# Serial.net
KiCad netlist of a schematic drawn in Altium Designer
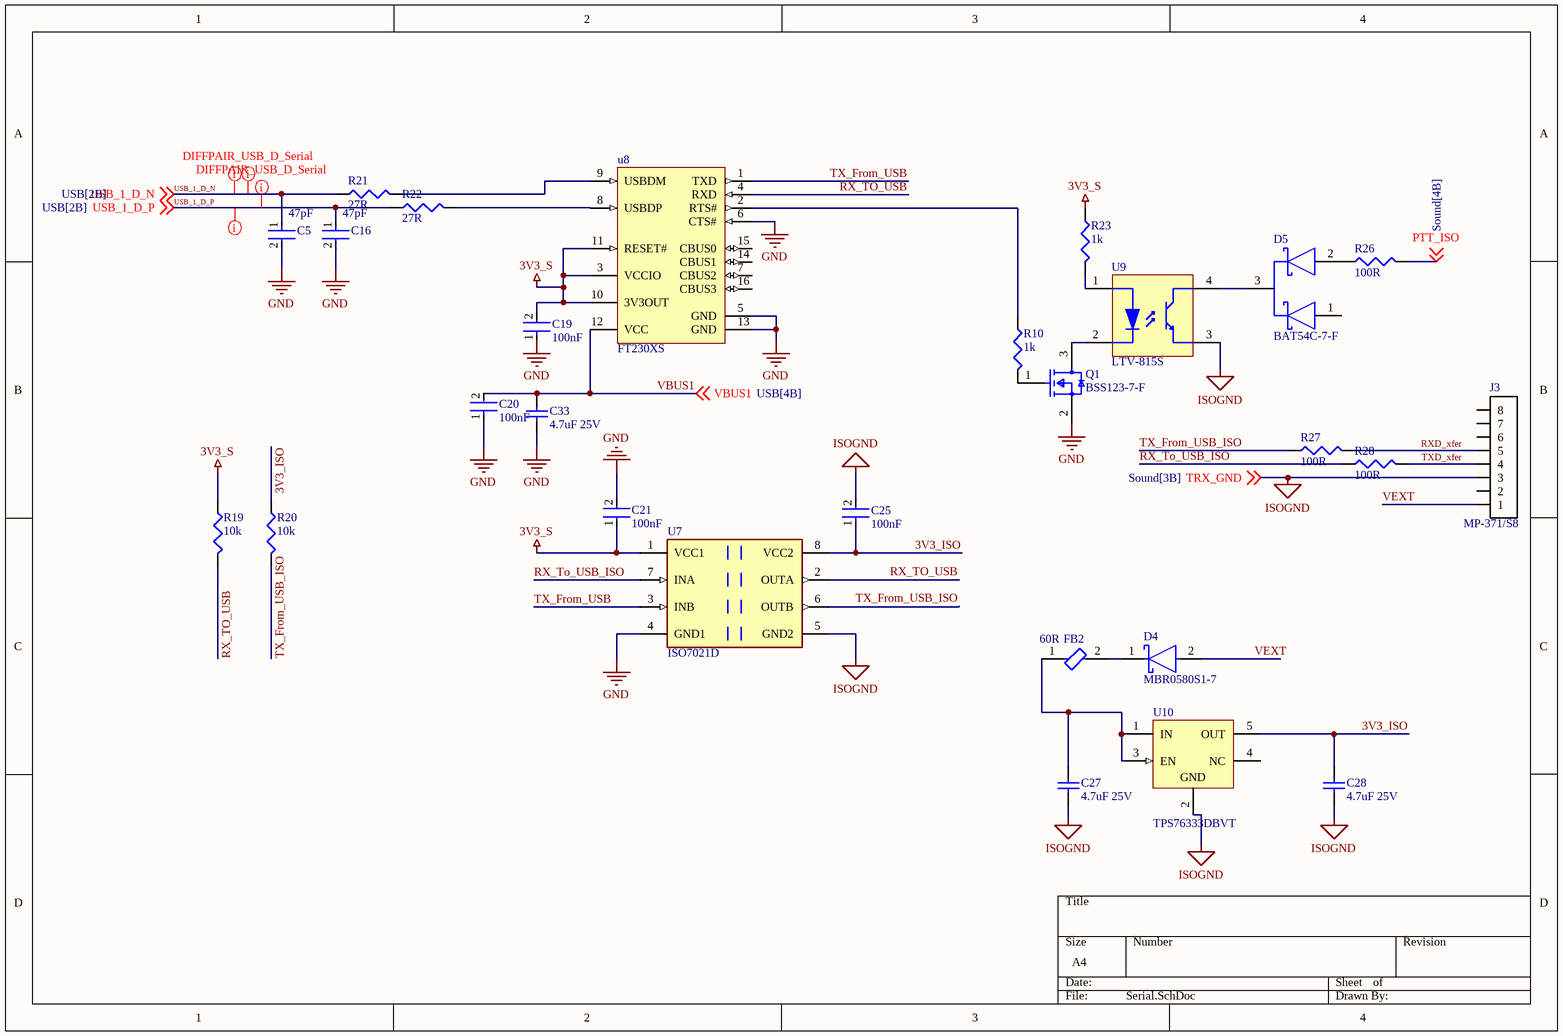
[diagram p0: Serial.SchDoc]

(export (version "E")
  (design (tool "Eeschema 10.0.6"))
  (components
    (comp (ref "C5")
      (value "CL10C470JC8NNNC")
      (footprint "FP-CL10-IPC_C")
      (description "Cap Ceramic 47pF 100V C0G ±5% Pad SMD 0603 +125°C T/R")
      (fields
        (field (name "TOLERANCE") "5%")
        (field (name "CAPACITANCE") "47pF")
        (field (name "JLCPCBPARTNUM") "C1671")
      )
      (libsource (lib "Altium Content Vault") (part "b4654b650e69147ec39a6b967a45e02"))
    )
    (comp (ref "C16")
      (value "CL10C470JC8NNNC")
      (footprint "FP-CL10-IPC_C")
      (description "Cap Ceramic 47pF 100V C0G ±5% Pad SMD 0603 +125°C T/R")
      (fields
        (field (name "TOLERANCE") "5%")
        (field (name "CAPACITANCE") "47pF")
        (field (name "JLCPCBPARTNUM") "C1671")
      )
      (libsource (lib "Altium Content Vault") (part "b4654b650e69147ec39a6b967a45e02"))
    )
    (comp (ref "C19")
      (value "CL10B104KC8NNNC")
      (footprint "FP-CL10-IPC_B")
      (description "Cap Ceramic 100nF 100V X7R ±10% Pad SMD 0603 +125°C T/R")
      (fields
        (field (name "TOLERANCE") "10%")
        (field (name "CAPACITANCE") "100nF")
        (field (name "JLCPCBPARTNUM") "C15725")
      )
      (libsource (lib "Altium Content Vault") (part "b4654b650e69147ec39a6b967a45e02"))
    )
    (comp (ref "C20")
      (value "CL10B104KC8NNNC")
      (footprint "FP-CL10-IPC_B")
      (description "Cap Ceramic 100nF 100V X7R ±10% Pad SMD 0603 +125°C T/R")
      (fields
        (field (name "TOLERANCE") "10%")
        (field (name "CAPACITANCE") "100nF")
        (field (name "JLCPCBPARTNUM") "C15725")
      )
      (libsource (lib "Altium Content Vault") (part "b4654b650e69147ec39a6b967a45e02"))
    )
    (comp (ref "C21")
      (value "CL10B104KC8NNNC")
      (footprint "FP-CL10-IPC_B")
      (description "Cap Ceramic 100nF 100V X7R ±10% Pad SMD 0603 +125°C T/R")
      (fields
        (field (name "TOLERANCE") "10%")
        (field (name "CAPACITANCE") "100nF")
        (field (name "JLCPCBPARTNUM") "C15725")
      )
      (libsource (lib "Altium Content Vault") (part "b4654b650e69147ec39a6b967a45e02"))
    )
    (comp (ref "C25")
      (value "CL10B104KC8NNNC")
      (footprint "FP-CL10-IPC_B")
      (description "Cap Ceramic 100nF 100V X7R ±10% Pad SMD 0603 +125°C T/R")
      (fields
        (field (name "TOLERANCE") "10%")
        (field (name "CAPACITANCE") "100nF")
        (field (name "JLCPCBPARTNUM") "C15725")
      )
      (libsource (lib "Altium Content Vault") (part "b4654b650e69147ec39a6b967a45e02"))
    )
    (comp (ref "C27")
      (value "4.7uF 25V")
      (footprint "CAPC1210(3225)220_M")
      (description "CAP 4.7uF 25V ±10% 1210 (3225 Metric) Thickness 2.2mm SMD")
      (fields (field (name "TOLERANCE") "Â±10%") (field (name "JLCPCBPARTNUM") "C86052"))
      (libsource (lib "Altium Content Vault") (part "CAP"))
    )
    (comp (ref "C28")
      (value "4.7uF 25V")
      (footprint "CAPC1210(3225)220_M")
      (description "CAP 4.7uF 25V ±10% 1210 (3225 Metric) Thickness 2.2mm SMD")
      (fields (field (name "TOLERANCE") "Â±10%") (field (name "JLCPCBPARTNUM") "C86052"))
      (libsource (lib "Altium Content Vault") (part "CAP"))
    )
    (comp (ref "C33")
      (value "4.7uF 25V")
      (footprint "CAPC1210(3225)220_M")
      (description "CAP 4.7uF 25V ±10% 1210 (3225 Metric) Thickness 2.2mm SMD")
      (fields (field (name "TOLERANCE") "Â±10%") (field (name "JLCPCBPARTNUM") "C86052"))
      (libsource (lib "Altium Content Vault") (part "CAP"))
    )
    (comp (ref "D4")
      (value "MBR0580S1-7")
      (footprint "FP-SOD123-MFG")
      (description "DIODE SCHOTTKY 80V 500MA SOD123")
      (fields
        (field (name "OCTOPART") "https://octopart.com/mbr0580s1-7-diodes+inc.-53081572")
        (field (name "MANUFACTURER") "Diodes")
      )
      (libsource (lib "Altium Content Vault") (part "1d6ec82d83fb6aee721767c19dac4b9"))
    )
    (comp (ref "D5")
      (value "BAT54C-7-F")
      (footprint "FP-SOT23-IPC_B")
      (description "DIODE ARRAY SCHOTTKY 30V SOT23-3")
      (fields (field (name "JLCPCBPARTNUM") "C134405"))
      (libsource (lib "Altium Content Vault") (part "3eac2aa0c1ac86323ecc23460aa29c6"))
    )
    (comp (ref "FB2")
      (value "BLM41PG600SN1L")
      (footprint "FP-BLM41-0_2-IPC_B")
      (description "Ferrite Bead, 1806, 60Ω @ 100MHz, 0.009Ω, 6A")
      (fields
        (field (name "TOLERANCE") "25%")
        (field (name "IMPEDANCE") "60R")
        (field (name "JLCPCBPARTNUM") "C85844")
      )
      (libsource (lib "Altium Content Vault") (part "5f30dd21d616792df468990f7003faa"))
    )
    (comp (ref "J3")
      (value "MP-371/S8")
      (footprint "MiniDIN8_TopSolder_Lumberg")
      (description "Miniature circular connectors MP-371/S8")
      (fields (field (name "DIGIKEY_PARTNUM") "2057-MDP-008-ND"))
      (libsource (lib "Schlib1") (part "MiniDin8_SMT"))
    )
    (comp (ref "Q1")
      (value "BSS123-7-F")
      (footprint "FP-SOT23-IPC_C")
      (description "MOSFET N-CH 100V 170MA SOT23-3")
      (fields
        (field (name "OCTOPART") "https://octopart.com/bss123-7-f-diodes+inc.-335886")
        (field (name "MANUFACTURER") "Diodes Incorporated")
      )
      (libsource (lib "Altium Content Vault") (part "1661867509f36a4ffa577829538a895"))
    )
    (comp (ref "R10")
      (value "1k")
      (footprint "J1-0603")
      (description "Resistor")
      (fields (field (name "JLCPCBPARTNUM") "C21190") (field (name "PUBLISHER") "Altium Limited"))
      (libsource (lib "Miscellaneous Devices") (part "Res3"))
    )
    (comp (ref "R19")
      (value "10k")
      (footprint "J1-0603")
      (description "Resistor")
      (fields (field (name "JLCPCBPARTNUM") "C25804") (field (name "PUBLISHER") "Altium Limited"))
      (libsource (lib "Miscellaneous Devices") (part "Res3"))
    )
    (comp (ref "R20")
      (value "10k")
      (footprint "J1-0603")
      (description "Resistor")
      (fields (field (name "JLCPCBPARTNUM") "C25804") (field (name "PUBLISHER") "Altium Limited"))
      (libsource (lib "Miscellaneous Devices") (part "Res3"))
    )
    (comp (ref "R21")
      (value "27R")
      (footprint "J1-0603")
      (description "Resistor")
      (fields (field (name "JLCPCBPARTNUM") "C192531") (field (name "PUBLISHER") "Altium Limited"))
      (libsource (lib "Miscellaneous Devices") (part "Res3"))
    )
    (comp (ref "R22")
      (value "27R")
      (footprint "J1-0603")
      (description "Resistor")
      (fields (field (name "JLCPCBPARTNUM") "C192531") (field (name "PUBLISHER") "Altium Limited"))
      (libsource (lib "Miscellaneous Devices") (part "Res3"))
    )
    (comp (ref "R23")
      (value "1k")
      (footprint "J1-0603")
      (description "Resistor")
      (fields (field (name "JLCPCBPARTNUM") "C21190") (field (name "PUBLISHER") "Altium Limited"))
      (libsource (lib "Miscellaneous Devices") (part "Res3"))
    )
    (comp (ref "R26")
      (value "100R")
      (footprint "J1-0603")
      (description "Resistor")
      (fields (field (name "JLCPCBPARTNUM") "C22775") (field (name "PUBLISHER") "Altium Limited"))
      (libsource (lib "Miscellaneous Devices") (part "Res3"))
    )
    (comp (ref "R27")
      (value "100R")
      (footprint "J1-0603")
      (description "Resistor")
      (fields (field (name "JLCPCBPARTNUM") "C22775") (field (name "PUBLISHER") "Altium Limited"))
      (libsource (lib "Miscellaneous Devices") (part "Res3"))
    )
    (comp (ref "R28")
      (value "100R")
      (footprint "J1-0603")
      (description "Resistor")
      (fields (field (name "JLCPCBPARTNUM") "C22775") (field (name "PUBLISHER") "Altium Limited"))
      (libsource (lib "Miscellaneous Devices") (part "Res3"))
    )
    (comp (ref "U7")
      (value "ISO7021D")
      (footprint "FP-D0008A-IPC_B")
      (description "DGTL ISO 3000VRMS 2CH GP 8SOIC")
      (libsource (lib "Altium Content Vault") (part "defe170305b380fc4992fd481d2aa34"))
    )
    (comp (ref "u8")
      (value "FT230XS")
      (footprint "FTDI-SSOP-16_L")
      (description "USB to Basic UART IC, 2.97 to 5.5 V, -40 to 85 degC, 16-Pin SSOP, RoHS")
      (fields (field (name "MANUFACTURER") "FTDI") (field (name "JLCPCBPARTNUM") "C69082"))
      (libsource (lib "Altium Content Vault") (part "FTDI-FT230XS-SSOP-16"))
    )
    (comp (ref "U9")
      (value "LTV-815S")
      (footprint "LTST-LTV-817S-4_V")
      (description "Photocoupler - Phototransistor Output, 35 V VCEO, -50 to 110 degC, 4-Pin SMD, RoHS, Tape and Reel")
      (fields (field (name "MANUFACTURER") "Lite-On") (field (name "JLCPCBPARTNUM") "C115455"))
      (libsource (lib "Altium Content Vault") (part "LTST-LTV-817-4"))
    )
    (comp (ref "U10")
      (value "TPS76333DBVT")
      (footprint "DBV0005A_N")
      (fields (field (name "MANUFACTURER") "Texas Instruments") (field (name "JLCPCBPARTNUM") "C7100"))
      (libsource (lib "Altium Content Vault") (part "TI-TXX7XXXX-5"))
    )
  )
  (nets
    (net (code "1") (name "/3V3_ISO") (class "Default")
      (node (ref "C25") (pin "1") (pinfunction "1_1") (pintype "passive"))
      (node (ref "C28") (pin "1") (pinfunction "1_1") (pintype "passive"))
      (node (ref "R20") (pin "1") (pinfunction "1_1") (pintype "passive"))
      (node (ref "U10") (pin "5") (pinfunction "OUT_5") (pintype "power_in"))
      (node (ref "U7") (pin "8") (pinfunction "VCC2_8") (pintype "power_in"))
    )
    (net (code "2") (name "/RXD_xfer") (class "Default")
      (node (ref "J3") (pin "5") (pinfunction "5_5") (pintype "passive"))
      (node (ref "R27") (pin "2") (pinfunction "2_2") (pintype "passive"))
    )
    (net (code "3") (name "/RX_TO_USB") (class "Default")
      (node (ref "R19") (pin "2") (pinfunction "2_2") (pintype "passive"))
      (node (ref "U7") (pin "2") (pinfunction "OUTA_2") (pintype "output"))
      (node (ref "u8") (pin "4") (pinfunction "RXD_4") (pintype "input"))
    )
    (net (code "4") (name "/RX_To_USB_ISO") (class "Default")
      (node (ref "R28") (pin "1") (pinfunction "1_1") (pintype "passive"))
      (node (ref "U7") (pin "7") (pinfunction "INA_7") (pintype "input"))
    )
    (net (code "5") (name "/TXD_xfer") (class "Default")
      (node (ref "J3") (pin "4") (pinfunction "4_4") (pintype "passive"))
      (node (ref "R28") (pin "2") (pinfunction "2_2") (pintype "passive"))
    )
    (net (code "6") (name "/TX_From_USB") (class "Default")
      (node (ref "U7") (pin "3") (pinfunction "INB_3") (pintype "input"))
      (node (ref "u8") (pin "1") (pinfunction "TXD_1") (pintype "output"))
    )
    (net (code "7") (name "/TX_From_USB_ISO") (class "Default")
      (node (ref "R20") (pin "2") (pinfunction "2_2") (pintype "passive"))
      (node (ref "R27") (pin "1") (pinfunction "1_1") (pintype "passive"))
      (node (ref "U7") (pin "6") (pinfunction "OUTB_6") (pintype "output"))
    )
    (net (code "8") (name "/VEXT") (class "Default")
      (node (ref "D4") (pin "2") (pinfunction "A_2") (pintype "passive"))
      (node (ref "J3") (pin "1") (pinfunction "1_1") (pintype "passive"))
    )
    (net (code "9") (name "3V3_S") (class "Default")
      (node (ref "C19") (pin "2") (pinfunction "2_2") (pintype "passive"))
      (node (ref "C21") (pin "1") (pinfunction "1_1") (pintype "passive"))
      (node (ref "R19") (pin "1") (pinfunction "1_1") (pintype "passive"))
      (node (ref "R23") (pin "1") (pinfunction "1_1") (pintype "passive"))
      (node (ref "U7") (pin "1") (pinfunction "VCC1_1") (pintype "power_in"))
      (node (ref "u8") (pin "10") (pinfunction "3V3OUT_10") (pintype "power_in"))
      (node (ref "u8") (pin "11") (pinfunction "RESET#_11") (pintype "input"))
      (node (ref "u8") (pin "3") (pinfunction "VCCIO_3") (pintype "power_in"))
    )
    (net (code "10") (name "GND") (class "Default")
      (node (ref "C16") (pin "2") (pinfunction "2_2") (pintype "passive"))
      (node (ref "C19") (pin "1") (pinfunction "1_1") (pintype "passive"))
      (node (ref "C20") (pin "1") (pinfunction "1_1") (pintype "passive"))
      (node (ref "C21") (pin "2") (pinfunction "2_2") (pintype "passive"))
      (node (ref "C33") (pin "2") (pinfunction "2_2") (pintype "passive"))
      (node (ref "C5") (pin "2") (pinfunction "2_2") (pintype "passive"))
      (node (ref "Q1") (pin "2") (pinfunction "S_2") (pintype "passive"))
      (node (ref "U7") (pin "4") (pinfunction "GND1_4") (pintype "power_in"))
      (node (ref "u8") (pin "13") (pinfunction "GND_13") (pintype "power_in"))
      (node (ref "u8") (pin "5") (pinfunction "GND_5") (pintype "power_in"))
      (node (ref "u8") (pin "6") (pinfunction "CTS#_6") (pintype "input"))
    )
    (net (code "11") (name "ISOGND") (class "Default")
      (node (ref "C25") (pin "2") (pinfunction "2_2") (pintype "passive"))
      (node (ref "C27") (pin "2") (pinfunction "2_2") (pintype "passive"))
      (node (ref "C28") (pin "2") (pinfunction "2_2") (pintype "passive"))
      (node (ref "J3") (pin "3") (pinfunction "3_3") (pintype "passive"))
      (node (ref "U10") (pin "2") (pinfunction "GND_2") (pintype "power_in"))
      (node (ref "U7") (pin "5") (pinfunction "GND2_5") (pintype "power_in"))
      (node (ref "U9") (pin "3") (pinfunction "EMITTER_3") (pintype "passive"))
    )
    (net (code "12") (name "Net-(D4-C)") (class "Default")
      (node (ref "D4") (pin "1") (pinfunction "C_1") (pintype "passive"))
      (node (ref "FB2") (pin "2") (pinfunction "2_2") (pintype "passive"))
    )
    (net (code "13") (name "Net-(D5-2_ANODE)") (class "Default")
      (node (ref "D5") (pin "2") (pinfunction "2_ANODE_2") (pintype "passive"))
      (node (ref "R26") (pin "1") (pinfunction "1_1") (pintype "passive"))
    )
    (net (code "14") (name "Net-(D5-COMMON_CATHODE)") (class "Default")
      (node (ref "D5") (pin "3") (pinfunction "COMMON_CATHODE_3") (pintype "passive"))
      (node (ref "U9") (pin "4") (pinfunction "COLLECTOR_4") (pintype "passive"))
    )
    (net (code "15") (name "Net-(Q1-D)") (class "Default")
      (node (ref "Q1") (pin "3") (pinfunction "D_3") (pintype "passive"))
      (node (ref "U9") (pin "2") (pinfunction "CATHODE_2") (pintype "passive"))
    )
    (net (code "16") (name "Net-(Q1-G)") (class "Default")
      (node (ref "Q1") (pin "1") (pinfunction "G_1") (pintype "passive"))
      (node (ref "R10") (pin "2") (pinfunction "2_2") (pintype "passive"))
    )
    (net (code "17") (name "Net-(U9-ANODE)") (class "Default")
      (node (ref "R23") (pin "2") (pinfunction "2_2") (pintype "passive"))
      (node (ref "U9") (pin "1") (pinfunction "ANODE_1") (pintype "passive"))
    )
    (net (code "18") (name "Net-(U10-EN)") (class "Default")
      (node (ref "C27") (pin "1") (pinfunction "1_1") (pintype "passive"))
      (node (ref "FB2") (pin "1") (pinfunction "1_1") (pintype "passive"))
      (node (ref "U10") (pin "1") (pinfunction "IN_1") (pintype "power_in"))
      (node (ref "U10") (pin "3") (pinfunction "EN_3") (pintype "input"))
    )
    (net (code "19") (name "Net-(u8-RTS#)") (class "Default")
      (node (ref "R10") (pin "1") (pinfunction "1_1") (pintype "passive"))
      (node (ref "u8") (pin "2") (pinfunction "RTS#_2") (pintype "output"))
    )
    (net (code "20") (name "Net-(u8-USBDM)") (class "Default")
      (node (ref "R21") (pin "2") (pinfunction "2_2") (pintype "passive"))
      (node (ref "u8") (pin "9") (pinfunction "USBDM_9") (pintype "input"))
    )
    (net (code "21") (name "Net-(u8-USBDP)") (class "Default")
      (node (ref "R22") (pin "2") (pinfunction "2_2") (pintype "passive"))
      (node (ref "u8") (pin "8") (pinfunction "USBDP_8") (pintype "input"))
    )
    (net (code "22") (name "PTT_ISO") (class "Default")
      (node (ref "R26") (pin "2") (pinfunction "2_2") (pintype "passive"))
    )
    (net (code "23") (name "USB_1_D_N") (class "Default")
      (node (ref "C5") (pin "1") (pinfunction "1_1") (pintype "passive"))
      (node (ref "R21") (pin "1") (pinfunction "1_1") (pintype "passive"))
    )
    (net (code "24") (name "USB_1_D_P") (class "Default")
      (node (ref "C16") (pin "1") (pinfunction "1_1") (pintype "passive"))
      (node (ref "R22") (pin "1") (pinfunction "1_1") (pintype "passive"))
    )
    (net (code "25") (name "VBUS1") (class "Default")
      (node (ref "C20") (pin "2") (pinfunction "2_2") (pintype "passive"))
      (node (ref "C33") (pin "1") (pinfunction "1_1") (pintype "passive"))
      (node (ref "u8") (pin "12") (pinfunction "VCC_12") (pintype "power_in"))
    )
    (net (code "26") (name "unconnected-(D5-1_ANODE-Pad1)") (class "Default")
      (node (ref "D5") (pin "1") (pinfunction "1_ANODE_1") (pintype "passive"))
    )
    (net (code "27") (name "unconnected-(J3-Pad2)") (class "Default")
      (node (ref "J3") (pin "2") (pinfunction "2_2") (pintype "passive"))
    )
    (net (code "28") (name "unconnected-(J3-Pad6)") (class "Default")
      (node (ref "J3") (pin "6") (pinfunction "6_6") (pintype "passive"))
    )
    (net (code "29") (name "unconnected-(J3-Pad7)") (class "Default")
      (node (ref "J3") (pin "7") (pinfunction "7_7") (pintype "passive"))
    )
    (net (code "30") (name "unconnected-(J3-Pad8)") (class "Default")
      (node (ref "J3") (pin "8") (pinfunction "8_8") (pintype "passive"))
    )
    (net (code "31") (name "unconnected-(U10-NC-Pad4)") (class "Default")
      (node (ref "U10") (pin "4") (pinfunction "NC_4") (pintype "passive"))
    )
    (net (code "32") (name "unconnected-(u8-CBUS0-Pad15)") (class "Default")
      (node (ref "u8") (pin "15") (pinfunction "CBUS0_15") (pintype "bidirectional"))
    )
    (net (code "33") (name "unconnected-(u8-CBUS1-Pad14)") (class "Default")
      (node (ref "u8") (pin "14") (pinfunction "CBUS1_14") (pintype "bidirectional"))
    )
    (net (code "34") (name "unconnected-(u8-CBUS2-Pad7)") (class "Default")
      (node (ref "u8") (pin "7") (pinfunction "CBUS2_7") (pintype "bidirectional"))
    )
    (net (code "35") (name "unconnected-(u8-CBUS3-Pad16)") (class "Default")
      (node (ref "u8") (pin "16") (pinfunction "CBUS3_16") (pintype "bidirectional"))
    )
  )
)
